# swimate_displayext.net
KiCad netlist of a schematic drawn in EAGLE
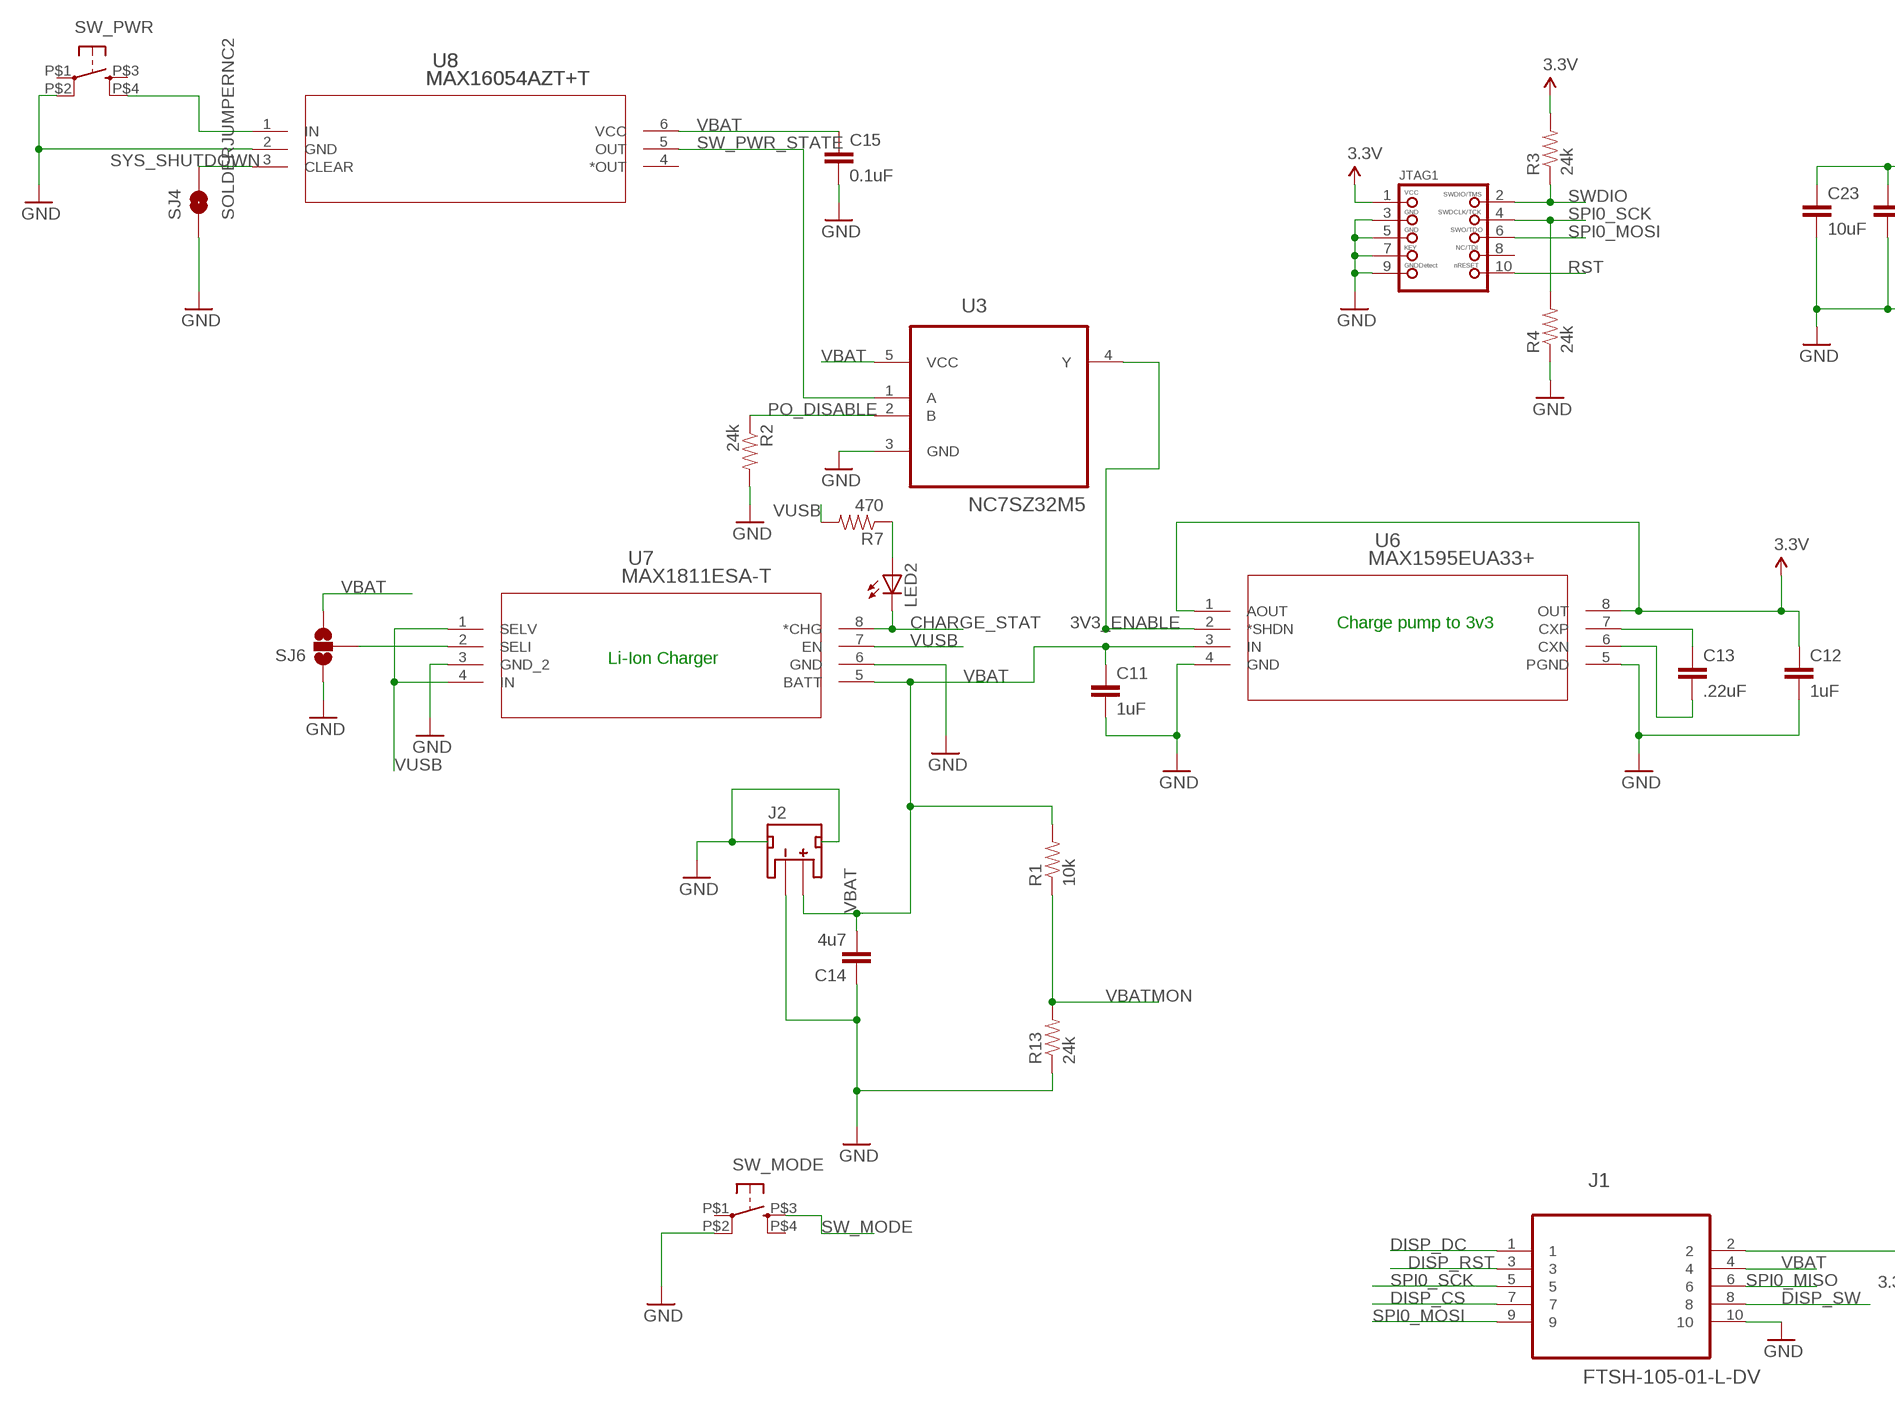
[diagram p0: schematic, sheet 1, part 1 of 2]
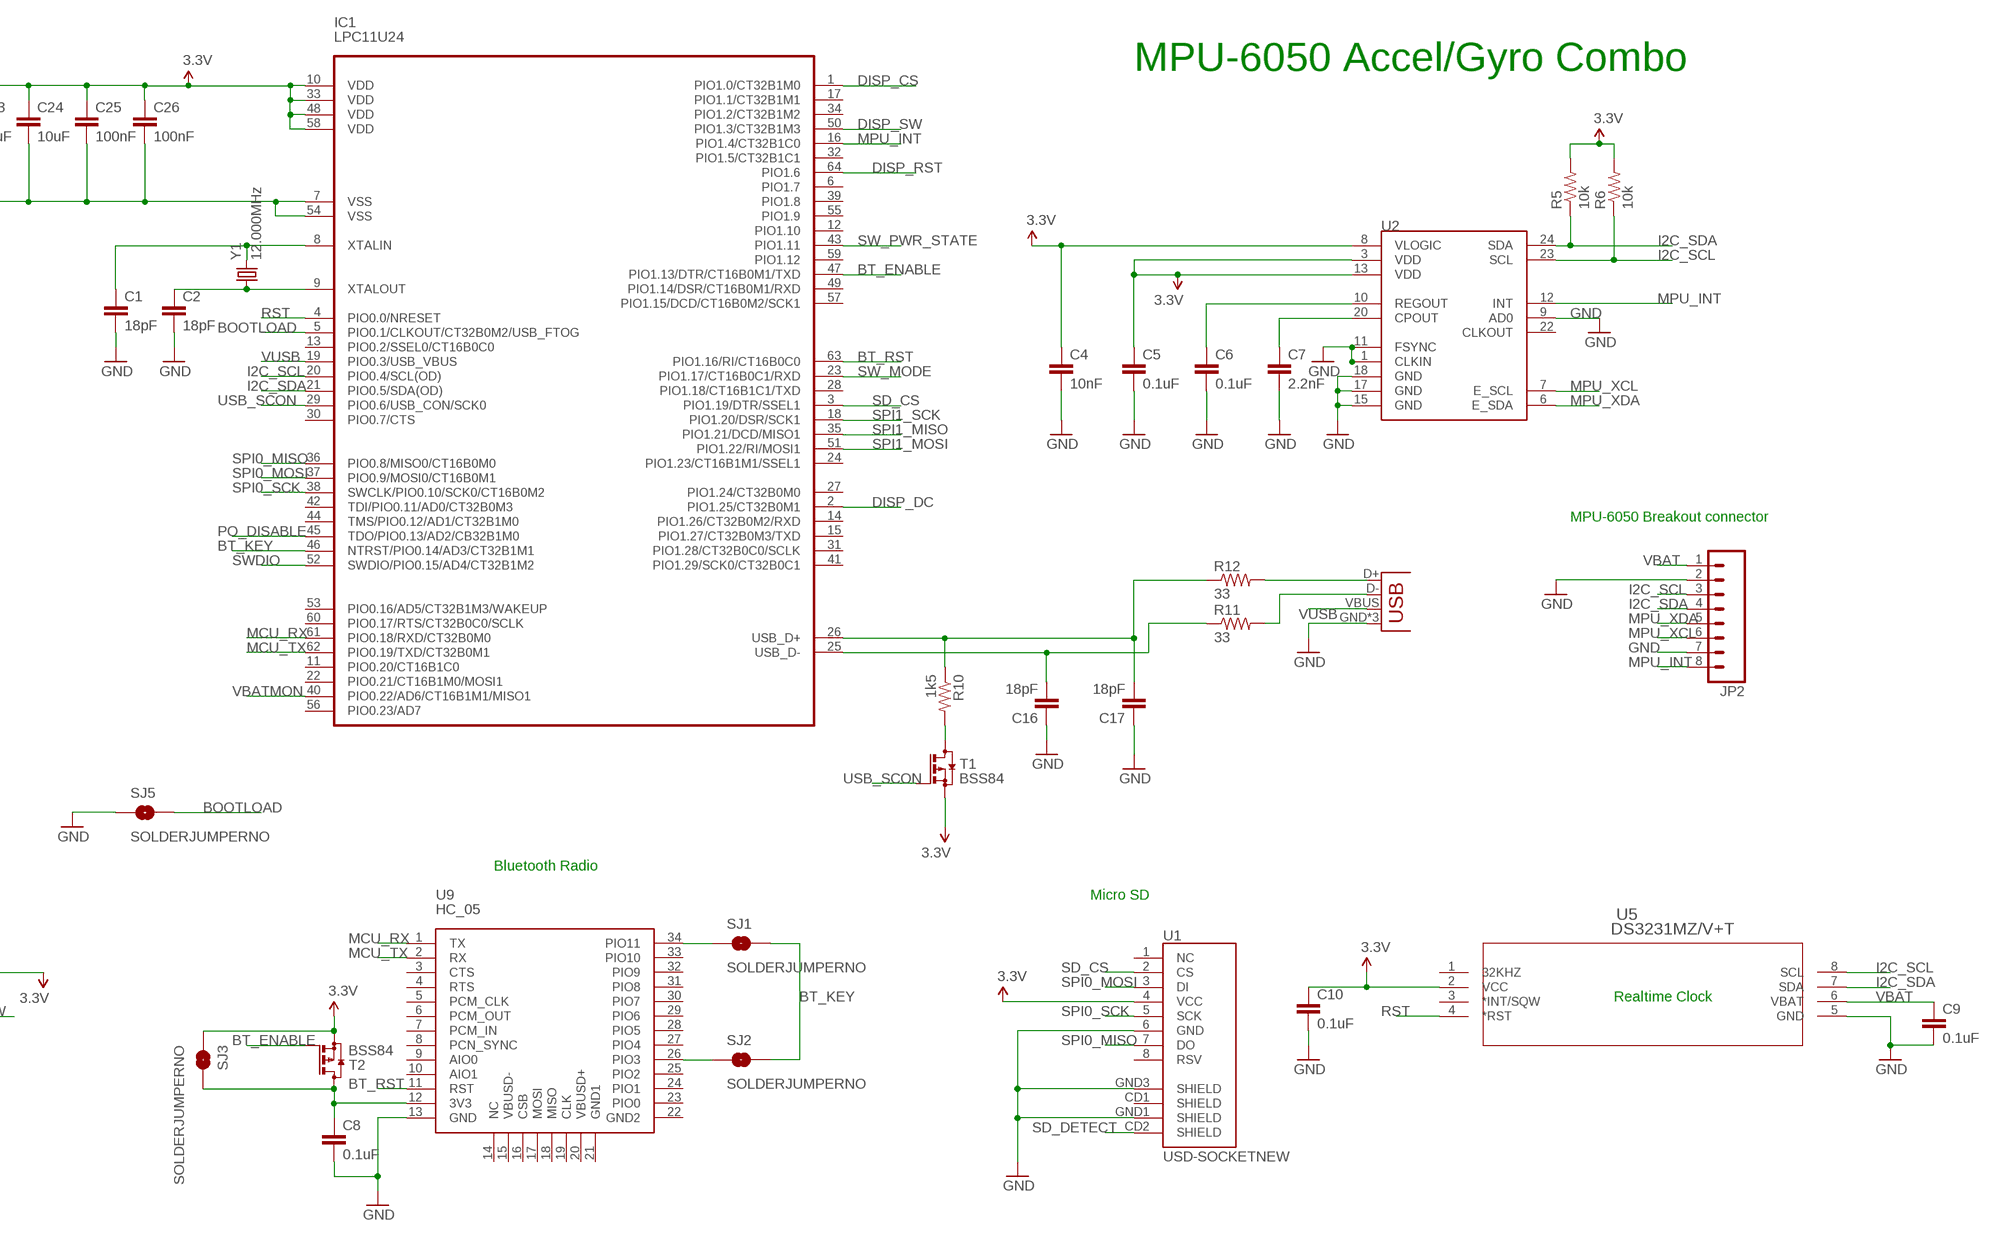
[diagram p1: schematic, sheet 1, part 2 of 2]

(export (version "E")
  (design (tool "Eeschema 10.0.6"))
  (components
    (comp (ref "C1")
      (value "18pF")
      (footprint "eagle-import:0805")
      (libsource (lib "eagle-import") (part "SparkFun-Passives_CAP0805"))
    )
    (comp (ref "C2")
      (value "18pF")
      (footprint "eagle-import:0805")
      (libsource (lib "eagle-import") (part "SparkFun-Passives_CAP0805"))
    )
    (comp (ref "C4")
      (value "10nF")
      (footprint "eagle-import:0805")
      (libsource (lib "eagle-import") (part "SparkFun-Passives_CAP0805"))
    )
    (comp (ref "C5")
      (value "0.1uF")
      (footprint "eagle-import:0805")
      (libsource (lib "eagle-import") (part "SparkFun-Passives_CAP0805"))
    )
    (comp (ref "C6")
      (value "0.1uF")
      (footprint "eagle-import:0805")
      (libsource (lib "eagle-import") (part "SparkFun-Passives_CAP0805"))
    )
    (comp (ref "C7")
      (value "2.2nF")
      (footprint "eagle-import:0805")
      (libsource (lib "eagle-import") (part "SparkFun-Passives_CAP0805"))
    )
    (comp (ref "C8")
      (value "0.1uF")
      (footprint "eagle-import:0805")
      (libsource (lib "eagle-import") (part "SparkFun-Passives_CAP0805"))
    )
    (comp (ref "C9")
      (value "0.1uF")
      (footprint "eagle-import:0805")
      (libsource (lib "eagle-import") (part "SparkFun-Passives_CAP0805"))
    )
    (comp (ref "C10")
      (value "0.1uF")
      (footprint "eagle-import:0805")
      (libsource (lib "eagle-import") (part "SparkFun-Passives_CAP0805"))
    )
    (comp (ref "C11")
      (value "1uF")
      (footprint "eagle-import:1206")
      (libsource (lib "eagle-import") (part "CAP1206"))
    )
    (comp (ref "C12")
      (value "1uF")
      (footprint "eagle-import:1206")
      (libsource (lib "eagle-import") (part "CAP1206"))
    )
    (comp (ref "C13")
      (value ".22uF")
      (footprint "eagle-import:0805")
      (libsource (lib "eagle-import") (part "SparkFun-Passives_CAP0805"))
    )
    (comp (ref "C14")
      (value "4u7")
      (footprint "eagle-import:1206")
      (libsource (lib "eagle-import") (part "SparkFun-Passives_CAP1206"))
    )
    (comp (ref "C15")
      (value "0.1uF")
      (footprint "eagle-import:0805")
      (libsource (lib "eagle-import") (part "SparkFun-Passives_CAP0805"))
    )
    (comp (ref "C16")
      (value "18pF")
      (footprint "eagle-import:0805")
      (libsource (lib "eagle-import") (part "SparkFun-Passives_CAP0805"))
    )
    (comp (ref "C17")
      (value "18pF")
      (footprint "eagle-import:0805")
      (libsource (lib "eagle-import") (part "SparkFun-Passives_CAP0805"))
    )
    (comp (ref "C23")
      (value "10uF")
      (footprint "eagle-import:0805")
      (libsource (lib "eagle-import") (part "CAP0805"))
    )
    (comp (ref "C24")
      (value "10uF")
      (footprint "eagle-import:0805")
      (libsource (lib "eagle-import") (part "CAP0805"))
    )
    (comp (ref "C25")
      (value "100nF")
      (footprint "eagle-import:0805")
      (libsource (lib "eagle-import") (part "CAP0805"))
    )
    (comp (ref "C26")
      (value "100nF")
      (footprint "eagle-import:0805")
      (libsource (lib "eagle-import") (part "CAP0805"))
    )
    (comp (ref "IC1")
      (value "LPC11U24")
      (footprint "eagle-import:MBED-ICS_LQFP64")
      (libsource (lib "eagle-import") (part "LPC11U24"))
    )
    (comp (ref "J1")
      (value "FTSH-105-01-L-DV")
      (footprint "eagle-import:SAMTEC_FTSH-105-01-L-DV")
      (libsource (lib "eagle-import") (part "FTSH-105-01-L-DV"))
    )
    (comp (ref "J2")
      (value "JST_2MM_MALE")
      (footprint "eagle-import:JST-2-SMD")
      (libsource (lib "eagle-import") (part "JST_2MM_MALE"))
    )
    (comp (ref "JP2")
      (value "M08")
      (footprint "eagle-import:1X08_PIN1_NO_SILK")
      (libsource (lib "eagle-import") (part "M08"))
    )
    (comp (ref "JP3")
      (value "USB-MICROB")
      (footprint "eagle-import:USB-MICROB")
      (libsource (lib "eagle-import") (part "USB-MICROB"))
    )
    (comp (ref "JTAG1")
      (value "JTAG-CORTEXM3")
      (footprint "eagle-import:2X05_1.27MM_SMT")
      (libsource (lib "eagle-import") (part "JTAG-CORTEXM3"))
    )
    (comp (ref "LED2")
      (value "LED0603")
      (footprint "eagle-import:LED-0603")
      (libsource (lib "eagle-import") (part "LED0603"))
    )
    (comp (ref "R1")
      (value "10k")
      (footprint "eagle-import:0603-RES")
      (libsource (lib "eagle-import") (part "RESISTOR0603-RES"))
    )
    (comp (ref "R2")
      (value "24k")
      (footprint "eagle-import:0805")
      (libsource (lib "eagle-import") (part "RESISTOR0805-RES"))
    )
    (comp (ref "R3")
      (value "24k")
      (footprint "eagle-import:0805")
      (libsource (lib "eagle-import") (part "RESISTOR0805-RES"))
    )
    (comp (ref "R4")
      (value "24k")
      (footprint "eagle-import:0805")
      (libsource (lib "eagle-import") (part "RESISTOR0805-RES"))
    )
    (comp (ref "R5")
      (value "10k")
      (footprint "eagle-import:0805")
      (libsource (lib "eagle-import") (part "RESISTOR0805-RES"))
    )
    (comp (ref "R6")
      (value "10k")
      (footprint "eagle-import:0805")
      (libsource (lib "eagle-import") (part "RESISTOR0805-RES"))
    )
    (comp (ref "R7")
      (value "470")
      (footprint "eagle-import:0805")
      (libsource (lib "eagle-import") (part "RESISTOR0805-RES"))
    )
    (comp (ref "R10")
      (value "1k5")
      (footprint "eagle-import:0805")
      (libsource (lib "eagle-import") (part "RESISTOR0805-RES"))
    )
    (comp (ref "R11")
      (value "33")
      (footprint "eagle-import:0805")
      (libsource (lib "eagle-import") (part "RESISTOR0805-RES"))
    )
    (comp (ref "R12")
      (value "33")
      (footprint "eagle-import:0805")
      (libsource (lib "eagle-import") (part "RESISTOR0805-RES"))
    )
    (comp (ref "R13")
      (value "24k")
      (footprint "eagle-import:0603-RES")
      (libsource (lib "eagle-import") (part "RESISTOR0603-RES"))
    )
    (comp (ref "SJ1")
      (value "SOLDERJUMPERNO")
      (footprint "eagle-import:SJ_2S-NO")
      (libsource (lib "eagle-import") (part "SOLDERJUMPERNO"))
    )
    (comp (ref "SJ2")
      (value "SOLDERJUMPERNO")
      (footprint "eagle-import:SJ_2S-NO")
      (libsource (lib "eagle-import") (part "SOLDERJUMPERNO"))
    )
    (comp (ref "SJ3")
      (value "SOLDERJUMPERNO")
      (footprint "eagle-import:SJ_2S-NO")
      (libsource (lib "eagle-import") (part "SOLDERJUMPERNO"))
    )
    (comp (ref "SJ4")
      (value "SOLDERJUMPERNC2")
      (footprint "eagle-import:SJ_2S-NOTRACE")
      (libsource (lib "eagle-import") (part "SOLDERJUMPERNC2"))
    )
    (comp (ref "SJ5")
      (value "SOLDERJUMPERNO")
      (footprint "eagle-import:SJ_2S-NO")
      (libsource (lib "eagle-import") (part "SOLDERJUMPERNO"))
    )
    (comp (ref "SJ6")
      (value "SOLDERJUMPER_2WAYS")
      (footprint "eagle-import:SJ_3")
      (libsource (lib "eagle-import") (part "SOLDERJUMPER_2WAYS"))
    )
    (comp (ref "SW_MODE")
      (value "TAC_SWITCHKSA_SEALED")
      (footprint "eagle-import:KSA_SEALED_TAC_SWITCH")
      (libsource (lib "eagle-import") (part "TAC_SWITCHKSA_SEALED"))
    )
    (comp (ref "SW_PWR")
      (value "TAC_SWITCHKSA_SEALED")
      (footprint "eagle-import:KSA_SEALED_TAC_SWITCH")
      (libsource (lib "eagle-import") (part "TAC_SWITCHKSA_SEALED"))
    )
    (comp (ref "T1")
      (value "BSS84")
      (footprint "eagle-import:SOT23")
      (libsource (lib "eagle-import") (part "BSS84"))
    )
    (comp (ref "T2")
      (value "BSS84")
      (footprint "eagle-import:SOT23")
      (libsource (lib "eagle-import") (part "BSS84"))
    )
    (comp (ref "U1")
      (value "USD-SOCKETNEW")
      (footprint "eagle-import:MICRO-SD-SOCKET-PP")
      (libsource (lib "eagle-import") (part "USD-SOCKETNEW"))
    )
    (comp (ref "U2")
      (value "MPU-9150QFN-24-NP")
      (footprint "eagle-import:QFN-24-NP")
      (libsource (lib "eagle-import") (part "MPU-9150QFN-24-NP"))
    )
    (comp (ref "U3")
      (value "NC7SZ32M5")
      (footprint "eagle-import:SOT95P280X145-5N")
      (libsource (lib "eagle-import") (part "NC7SZ32M5"))
    )
    (comp (ref "U5")
      (value "DS3231MZ/V+T")
      (footprint "eagle-import:21-0041B_8")
      (libsource (lib "eagle-import") (part "DS3231MZ/V+T"))
    )
    (comp (ref "U6")
      (value "MAX1595EUA33+")
      (footprint "eagle-import:21-0036K")
      (libsource (lib "eagle-import") (part "MAX1595EUA33+"))
    )
    (comp (ref "U7")
      (value "MAX1811ESA-T")
      (footprint "eagle-import:21-0041B_8")
      (libsource (lib "eagle-import") (part "MAX1811ESA-T"))
    )
    (comp (ref "U8")
      (value "MAX16054AZT+T")
      (footprint "eagle-import:21-0114C")
      (libsource (lib "eagle-import") (part "MAX16054AZT+T"))
    )
    (comp (ref "U9")
      (value "HC_05")
      (footprint "eagle-import:BLUETOOTH_SMD")
      (libsource (lib "eagle-import") (part "HC_05"))
    )
    (comp (ref "Y1")
      (value "12.000MHz")
      (footprint "eagle-import:CRYSTAL-SMD-10.5X4.8-2PIN")
      (libsource (lib "eagle-import") (part "CRYSTAL10.5X4.8"))
    )
  )
  (nets
    (net (code "1") (name "/3V3_ENABLE") (class "Default")
      (node (ref "U3") (pin "4") (pinfunction "Y_4") (pintype "output"))
      (node (ref "U6") (pin "2") (pinfunction "*SHDN_2") (pintype "passive"))
    )
    (net (code "2") (name "/BOOTLOAD") (class "Default")
      (node (ref "IC1") (pin "5") (pinfunction "PIO0.1/CLKOUT/CT32B0M2/USB_FTOG_5") (pintype "bidirectional"))
      (node (ref "SJ5") (pin "2") (pinfunction "2_2") (pintype "passive"))
    )
    (net (code "3") (name "/BT_ENABLE") (class "Default")
      (node (ref "IC1") (pin "47") (pinfunction "PIO1.13/DTR/CT16B0M1/TXD_47") (pintype "bidirectional"))
      (node (ref "T2") (pin "1") (pinfunction "G_1") (pintype "passive"))
    )
    (net (code "4") (name "/BT_KEY") (class "Default")
      (node (ref "IC1") (pin "46") (pinfunction "NTRST/PIO0.14/AD3/CT32B1M1_46") (pintype "bidirectional"))
      (node (ref "SJ1") (pin "2") (pinfunction "2_2") (pintype "passive"))
      (node (ref "SJ2") (pin "2") (pinfunction "2_2") (pintype "passive"))
    )
    (net (code "5") (name "/BT_RST") (class "Default")
      (node (ref "IC1") (pin "63") (pinfunction "PIO1.16/RI/CT16B0C0_63") (pintype "bidirectional"))
      (node (ref "U9") (pin "11") (pinfunction "RST_11") (pintype "bidirectional"))
    )
    (net (code "6") (name "/CHARGE_STAT") (class "Default")
      (node (ref "LED2") (pin "C") (pinfunction "C_C") (pintype "passive"))
      (node (ref "U7") (pin "8") (pinfunction "*CHG_8") (pintype "bidirectional"))
    )
    (net (code "7") (name "/DISP_CS") (class "Default")
      (node (ref "IC1") (pin "1") (pinfunction "PIO1.0/CT32B1M0_1") (pintype "bidirectional"))
      (node (ref "J1") (pin "7") (pinfunction "7_7") (pintype "passive"))
    )
    (net (code "8") (name "/DISP_DC") (class "Default")
      (node (ref "IC1") (pin "2") (pinfunction "PIO1.25/CT32B0M1_2") (pintype "bidirectional"))
      (node (ref "J1") (pin "1") (pinfunction "1_1") (pintype "passive"))
    )
    (net (code "9") (name "/DISP_RST") (class "Default")
      (node (ref "IC1") (pin "64") (pinfunction "PIO1.6_64") (pintype "bidirectional"))
      (node (ref "J1") (pin "3") (pinfunction "3_3") (pintype "passive"))
    )
    (net (code "10") (name "/DISP_SW") (class "Default")
      (node (ref "IC1") (pin "50") (pinfunction "PIO1.3/CT32B1M3_50") (pintype "bidirectional"))
      (node (ref "J1") (pin "8") (pinfunction "8_8") (pintype "passive"))
    )
    (net (code "11") (name "/I2C_SCL") (class "Default")
      (node (ref "IC1") (pin "20") (pinfunction "PIO0.4/SCL(OD)_20") (pintype "bidirectional"))
      (node (ref "JP2") (pin "3") (pinfunction "3_3") (pintype "passive"))
      (node (ref "R6") (pin "1") (pinfunction "1_1") (pintype "passive"))
      (node (ref "U2") (pin "23") (pinfunction "SCL_23") (pintype "bidirectional"))
      (node (ref "U5") (pin "8") (pinfunction "SCL_8") (pintype "passive"))
    )
    (net (code "12") (name "/I2C_SDA") (class "Default")
      (node (ref "IC1") (pin "21") (pinfunction "PIO0.5/SDA(OD)_21") (pintype "bidirectional"))
      (node (ref "JP2") (pin "4") (pinfunction "4_4") (pintype "passive"))
      (node (ref "R5") (pin "1") (pinfunction "1_1") (pintype "passive"))
      (node (ref "U2") (pin "24") (pinfunction "SDA_24") (pintype "bidirectional"))
      (node (ref "U5") (pin "7") (pinfunction "SDA_7") (pintype "passive"))
    )
    (net (code "13") (name "/MCU_RX") (class "Default")
      (node (ref "IC1") (pin "61") (pinfunction "PIO0.18/RXD/CT32B0M0_61") (pintype "bidirectional"))
      (node (ref "U9") (pin "1") (pinfunction "TX_1") (pintype "bidirectional"))
    )
    (net (code "14") (name "/MCU_TX") (class "Default")
      (node (ref "IC1") (pin "62") (pinfunction "PIO0.19/TXD/CT32B0M1_62") (pintype "bidirectional"))
      (node (ref "U9") (pin "2") (pinfunction "RX_2") (pintype "bidirectional"))
    )
    (net (code "15") (name "/MPU_INT") (class "Default")
      (node (ref "IC1") (pin "16") (pinfunction "PIO1.4/CT32B1C0_16") (pintype "bidirectional"))
      (node (ref "JP2") (pin "8") (pinfunction "8_8") (pintype "passive"))
      (node (ref "U2") (pin "12") (pinfunction "INT_12") (pintype "bidirectional"))
    )
    (net (code "16") (name "/MPU_XCL") (class "Default")
      (node (ref "JP2") (pin "6") (pinfunction "6_6") (pintype "passive"))
      (node (ref "U2") (pin "7") (pinfunction "E_SCL_7") (pintype "bidirectional"))
    )
    (net (code "17") (name "/MPU_XDA") (class "Default")
      (node (ref "JP2") (pin "5") (pinfunction "5_5") (pintype "passive"))
      (node (ref "U2") (pin "6") (pinfunction "E_SDA_6") (pintype "bidirectional"))
    )
    (net (code "18") (name "/PO_DISABLE") (class "Default")
      (node (ref "IC1") (pin "45") (pinfunction "TDO/PIO0.13/AD2/CB32B1M0_45") (pintype "bidirectional"))
      (node (ref "R2") (pin "1") (pinfunction "1_1") (pintype "passive"))
      (node (ref "U3") (pin "2") (pinfunction "B_2") (pintype "input"))
    )
    (net (code "19") (name "/RST") (class "Default")
      (node (ref "IC1") (pin "4") (pinfunction "PIO0.0/NRESET_4") (pintype "bidirectional"))
      (node (ref "JTAG1") (pin "10") (pinfunction "10_10") (pintype "passive"))
      (node (ref "U5") (pin "4") (pinfunction "*RST_4") (pintype "passive"))
    )
    (net (code "20") (name "/SD_CS") (class "Default")
      (node (ref "IC1") (pin "3") (pinfunction "PIO1.19/DTR/SSEL1_3") (pintype "bidirectional"))
      (node (ref "U1") (pin "2") (pinfunction "CS_2") (pintype "bidirectional"))
    )
    (net (code "21") (name "/SD_DETECT") (class "Default")
      (node (ref "U1") (pin "CD2") (pinfunction "SHIELD_CD2") (pintype "bidirectional"))
    )
    (net (code "22") (name "/SPI0_MISO") (class "Default")
      (node (ref "IC1") (pin "36") (pinfunction "PIO0.8/MISO0/CT16B0M0_36") (pintype "bidirectional"))
      (node (ref "J1") (pin "6") (pinfunction "6_6") (pintype "passive"))
      (node (ref "U1") (pin "7") (pinfunction "DO_7") (pintype "bidirectional"))
    )
    (net (code "23") (name "/SPI0_MOSI") (class "Default")
      (node (ref "IC1") (pin "37") (pinfunction "PIO0.9/MOSI0/CT16B0M1_37") (pintype "bidirectional"))
      (node (ref "J1") (pin "9") (pinfunction "9_9") (pintype "passive"))
      (node (ref "JTAG1") (pin "6") (pinfunction "6_6") (pintype "passive"))
      (node (ref "U1") (pin "3") (pinfunction "DI_3") (pintype "bidirectional"))
    )
    (net (code "24") (name "/SPI0_SCK") (class "Default")
      (node (ref "IC1") (pin "38") (pinfunction "SWCLK/PIO0.10/SCK0/CT16B0M2_38") (pintype "bidirectional"))
      (node (ref "J1") (pin "5") (pinfunction "5_5") (pintype "passive"))
      (node (ref "JTAG1") (pin "4") (pinfunction "4_4") (pintype "passive"))
      (node (ref "R4") (pin "2") (pinfunction "2_2") (pintype "passive"))
      (node (ref "U1") (pin "5") (pinfunction "SCK_5") (pintype "bidirectional"))
    )
    (net (code "25") (name "/SPI1_MISO") (class "Default")
      (node (ref "IC1") (pin "35") (pinfunction "PIO1.21/DCD/MISO1_35") (pintype "bidirectional"))
    )
    (net (code "26") (name "/SPI1_MOSI") (class "Default")
      (node (ref "IC1") (pin "51") (pinfunction "PIO1.22/RI/MOSI1_51") (pintype "bidirectional"))
    )
    (net (code "27") (name "/SPI1_SCK") (class "Default")
      (node (ref "IC1") (pin "18") (pinfunction "PIO1.20/DSR/SCK1_18") (pintype "bidirectional"))
    )
    (net (code "28") (name "/SWDIO") (class "Default")
      (node (ref "IC1") (pin "52") (pinfunction "SWDIO/PIO0.15/AD4/CT32B1M2_52") (pintype "bidirectional"))
      (node (ref "JTAG1") (pin "2") (pinfunction "2_2") (pintype "passive"))
      (node (ref "R3") (pin "1") (pinfunction "1_1") (pintype "passive"))
    )
    (net (code "29") (name "/SW_MODE") (class "Default")
      (node (ref "IC1") (pin "23") (pinfunction "PIO1.17/CT16B0C1/RXD_23") (pintype "bidirectional"))
      (node (ref "SW_MODE") (pin "P$3") (pinfunction "3_P$3") (pintype "passive"))
    )
    (net (code "30") (name "/SW_PWR_STATE") (class "Default")
      (node (ref "IC1") (pin "43") (pinfunction "PIO1.11_43") (pintype "bidirectional"))
      (node (ref "U3") (pin "1") (pinfunction "A_1") (pintype "input"))
      (node (ref "U8") (pin "5") (pinfunction "OUT_5") (pintype "output"))
    )
    (net (code "31") (name "/SYS_SHUTDOWN") (class "Default")
      (node (ref "SJ4") (pin "2") (pinfunction "2_2") (pintype "passive"))
      (node (ref "U8") (pin "3") (pinfunction "CLEAR_3") (pintype "bidirectional"))
    )
    (net (code "32") (name "/USB_SCON") (class "Default")
      (node (ref "IC1") (pin "29") (pinfunction "PIO0.6/USB_CON/SCK0_29") (pintype "bidirectional"))
      (node (ref "T1") (pin "1") (pinfunction "G_1") (pintype "passive"))
    )
    (net (code "33") (name "/VBAT") (class "Default")
      (node (ref "C11") (pin "1") (pinfunction "1_1") (pintype "passive"))
      (node (ref "C14") (pin "2") (pinfunction "2_2") (pintype "passive"))
      (node (ref "C15") (pin "1") (pinfunction "1_1") (pintype "passive"))
      (node (ref "C9") (pin "1") (pinfunction "1_1") (pintype "passive"))
      (node (ref "J1") (pin "4") (pinfunction "4_4") (pintype "passive"))
      (node (ref "J2") (pin "2") (pinfunction "+_2") (pintype "bidirectional"))
      (node (ref "JP2") (pin "1") (pinfunction "1_1") (pintype "passive"))
      (node (ref "R1") (pin "2") (pinfunction "2_2") (pintype "passive"))
      (node (ref "SJ6") (pin "3") (pinfunction "3_3") (pintype "passive"))
      (node (ref "U3") (pin "5") (pinfunction "VCC_5") (pintype "power_in"))
      (node (ref "U5") (pin "6") (pinfunction "VBAT_6") (pintype "power_in"))
      (node (ref "U6") (pin "3") (pinfunction "IN_3") (pintype "input"))
      (node (ref "U7") (pin "5") (pinfunction "BATT_5") (pintype "bidirectional"))
      (node (ref "U8") (pin "6") (pinfunction "VCC_6") (pintype "power_in"))
    )
    (net (code "34") (name "/VBATMON") (class "Default")
      (node (ref "IC1") (pin "40") (pinfunction "PIO0.22/AD6/CT16B1M1/MISO1_40") (pintype "bidirectional"))
      (node (ref "R1") (pin "1") (pinfunction "1_1") (pintype "passive"))
      (node (ref "R13") (pin "2") (pinfunction "2_2") (pintype "passive"))
    )
    (net (code "35") (name "/VUSB") (class "Default")
      (node (ref "IC1") (pin "19") (pinfunction "PIO0.3/USB_VBUS_19") (pintype "bidirectional"))
      (node (ref "JP3") (pin "VBUS") (pinfunction "VBUS_VBUS") (pintype "bidirectional"))
      (node (ref "R7") (pin "2") (pinfunction "2_2") (pintype "passive"))
      (node (ref "U7") (pin "1") (pinfunction "SELV_1") (pintype "bidirectional"))
      (node (ref "U7") (pin "4") (pinfunction "IN_4") (pintype "input"))
      (node (ref "U7") (pin "7") (pinfunction "EN_7") (pintype "bidirectional"))
    )
    (net (code "36") (name "3.3V") (class "Default")
      (node (ref "C10") (pin "1") (pinfunction "1_1") (pintype "passive"))
      (node (ref "C12") (pin "1") (pinfunction "1_1") (pintype "passive"))
      (node (ref "C23") (pin "1") (pinfunction "1_1") (pintype "passive"))
      (node (ref "C24") (pin "1") (pinfunction "1_1") (pintype "passive"))
      (node (ref "C25") (pin "1") (pinfunction "1_1") (pintype "passive"))
      (node (ref "C26") (pin "1") (pinfunction "1_1") (pintype "passive"))
      (node (ref "C4") (pin "1") (pinfunction "1_1") (pintype "passive"))
      (node (ref "C5") (pin "1") (pinfunction "1_1") (pintype "passive"))
      (node (ref "IC1") (pin "10") (pinfunction "VDD_10") (pintype "bidirectional"))
      (node (ref "IC1") (pin "33") (pinfunction "VDD_33") (pintype "bidirectional"))
      (node (ref "IC1") (pin "48") (pinfunction "VDD_48") (pintype "bidirectional"))
      (node (ref "IC1") (pin "58") (pinfunction "VDD_58") (pintype "bidirectional"))
      (node (ref "J1") (pin "2") (pinfunction "2_2") (pintype "passive"))
      (node (ref "JTAG1") (pin "1") (pinfunction "1_1") (pintype "passive"))
      (node (ref "R3") (pin "2") (pinfunction "2_2") (pintype "passive"))
      (node (ref "R5") (pin "2") (pinfunction "2_2") (pintype "passive"))
      (node (ref "R6") (pin "2") (pinfunction "2_2") (pintype "passive"))
      (node (ref "SJ3") (pin "1") (pinfunction "1_1") (pintype "passive"))
      (node (ref "T1") (pin "2") (pinfunction "S_2") (pintype "passive"))
      (node (ref "T2") (pin "2") (pinfunction "S_2") (pintype "passive"))
      (node (ref "U1") (pin "4") (pinfunction "VCC_4") (pintype "bidirectional"))
      (node (ref "U2") (pin "13") (pinfunction "VDD_13") (pintype "bidirectional"))
      (node (ref "U2") (pin "3") (pinfunction "VDD_3") (pintype "bidirectional"))
      (node (ref "U2") (pin "8") (pinfunction "VLOGIC_8") (pintype "bidirectional"))
      (node (ref "U5") (pin "2") (pinfunction "VCC_2") (pintype "power_in"))
      (node (ref "U6") (pin "1") (pinfunction "AOUT_1") (pintype "output"))
      (node (ref "U6") (pin "8") (pinfunction "OUT_8") (pintype "output"))
    )
    (net (code "37") (name "GND") (class "Default")
      (node (ref "C1") (pin "2") (pinfunction "2_2") (pintype "passive"))
      (node (ref "C10") (pin "2") (pinfunction "2_2") (pintype "passive"))
      (node (ref "C11") (pin "2") (pinfunction "2_2") (pintype "passive"))
      (node (ref "C12") (pin "2") (pinfunction "2_2") (pintype "passive"))
      (node (ref "C14") (pin "1") (pinfunction "1_1") (pintype "passive"))
      (node (ref "C15") (pin "2") (pinfunction "2_2") (pintype "passive"))
      (node (ref "C16") (pin "1") (pinfunction "1_1") (pintype "passive"))
      (node (ref "C17") (pin "1") (pinfunction "1_1") (pintype "passive"))
      (node (ref "C2") (pin "2") (pinfunction "2_2") (pintype "passive"))
      (node (ref "C23") (pin "2") (pinfunction "2_2") (pintype "passive"))
      (node (ref "C24") (pin "2") (pinfunction "2_2") (pintype "passive"))
      (node (ref "C25") (pin "2") (pinfunction "2_2") (pintype "passive"))
      (node (ref "C26") (pin "2") (pinfunction "2_2") (pintype "passive"))
      (node (ref "C4") (pin "2") (pinfunction "2_2") (pintype "passive"))
      (node (ref "C5") (pin "2") (pinfunction "2_2") (pintype "passive"))
      (node (ref "C6") (pin "2") (pinfunction "2_2") (pintype "passive"))
      (node (ref "C7") (pin "2") (pinfunction "2_2") (pintype "passive"))
      (node (ref "C8") (pin "2") (pinfunction "2_2") (pintype "passive"))
      (node (ref "C9") (pin "2") (pinfunction "2_2") (pintype "passive"))
      (node (ref "IC1") (pin "54") (pinfunction "VSS_54") (pintype "bidirectional"))
      (node (ref "IC1") (pin "7") (pinfunction "VSS_7") (pintype "bidirectional"))
      (node (ref "J1") (pin "10") (pinfunction "10_10") (pintype "passive"))
      (node (ref "J2") (pin "1") (pinfunction "-_1") (pintype "bidirectional"))
      (node (ref "J2") (pin "NC1") (pinfunction "PAD1_NC1") (pintype "bidirectional"))
      (node (ref "J2") (pin "NC2") (pinfunction "PAD2_NC2") (pintype "bidirectional"))
      (node (ref "JP2") (pin "2") (pinfunction "2_2") (pintype "passive"))
      (node (ref "JP2") (pin "7") (pinfunction "7_7") (pintype "passive"))
      (node (ref "JP3") (pin "GND") (pinfunction "GND_GND") (pintype "bidirectional"))
      (node (ref "JP3") (pin "MT1") (pinfunction "GND_MT1") (pintype "bidirectional"))
      (node (ref "JP3") (pin "MT2") (pinfunction "GND_MT2") (pintype "bidirectional"))
      (node (ref "JTAG1") (pin "3") (pinfunction "3_3") (pintype "passive"))
      (node (ref "JTAG1") (pin "5") (pinfunction "5_5") (pintype "passive"))
      (node (ref "JTAG1") (pin "7") (pinfunction "7_7") (pintype "passive"))
      (node (ref "JTAG1") (pin "9") (pinfunction "9_9") (pintype "passive"))
      (node (ref "R13") (pin "1") (pinfunction "1_1") (pintype "passive"))
      (node (ref "R2") (pin "2") (pinfunction "2_2") (pintype "passive"))
      (node (ref "R4") (pin "1") (pinfunction "1_1") (pintype "passive"))
      (node (ref "SJ4") (pin "1") (pinfunction "1_1") (pintype "passive"))
      (node (ref "SJ5") (pin "1") (pinfunction "1_1") (pintype "passive"))
      (node (ref "SJ6") (pin "1") (pinfunction "1_1") (pintype "passive"))
      (node (ref "SW_MODE") (pin "P$2") (pinfunction "2_P$2") (pintype "passive"))
      (node (ref "SW_PWR") (pin "P$2") (pinfunction "2_P$2") (pintype "passive"))
      (node (ref "U1") (pin "6") (pinfunction "GND_6") (pintype "bidirectional"))
      (node (ref "U1") (pin "GND1") (pinfunction "SHIELD_GND1") (pintype "bidirectional"))
      (node (ref "U1") (pin "GND3") (pinfunction "SHIELD_GND3") (pintype "bidirectional"))
      (node (ref "U2") (pin "1") (pinfunction "CLKIN_1") (pintype "bidirectional"))
      (node (ref "U2") (pin "11") (pinfunction "FSYNC_11") (pintype "bidirectional"))
      (node (ref "U2") (pin "15") (pinfunction "GND_15") (pintype "bidirectional"))
      (node (ref "U2") (pin "17") (pinfunction "GND_17") (pintype "bidirectional"))
      (node (ref "U2") (pin "18") (pinfunction "GND_18") (pintype "bidirectional"))
      (node (ref "U2") (pin "9") (pinfunction "AD0_9") (pintype "bidirectional"))
      (node (ref "U3") (pin "3") (pinfunction "GND_3") (pintype "passive"))
      (node (ref "U5") (pin "5") (pinfunction "GND_5") (pintype "power_in"))
      (node (ref "U6") (pin "4") (pinfunction "GND_4") (pintype "power_in"))
      (node (ref "U6") (pin "5") (pinfunction "PGND_5") (pintype "power_in"))
      (node (ref "U7") (pin "3") (pinfunction "GND_2_3") (pintype "power_in"))
      (node (ref "U7") (pin "6") (pinfunction "GND_6") (pintype "power_in"))
      (node (ref "U8") (pin "2") (pinfunction "GND_2") (pintype "power_in"))
      (node (ref "U9") (pin "13") (pinfunction "GND_13") (pintype "bidirectional"))
    )
    (net (code "38") (name "Net-(IC1-USB_D+)") (class "Default")
      (node (ref "C17") (pin "2") (pinfunction "2_2") (pintype "passive"))
      (node (ref "IC1") (pin "26") (pinfunction "USB_D+_26") (pintype "bidirectional"))
      (node (ref "R10") (pin "1") (pinfunction "1_1") (pintype "passive"))
      (node (ref "R12") (pin "1") (pinfunction "1_1") (pintype "passive"))
    )
    (net (code "39") (name "Net-(IC1-USB_D-)") (class "Default")
      (node (ref "C16") (pin "2") (pinfunction "2_2") (pintype "passive"))
      (node (ref "IC1") (pin "25") (pinfunction "USB_D-_25") (pintype "bidirectional"))
      (node (ref "R11") (pin "1") (pinfunction "1_1") (pintype "passive"))
    )
    (net (code "40") (name "Net-(IC1-XTALIN)") (class "Default")
      (node (ref "C1") (pin "1") (pinfunction "1_1") (pintype "passive"))
      (node (ref "IC1") (pin "8") (pinfunction "XTALIN_8") (pintype "bidirectional"))
      (node (ref "Y1") (pin "P$2") (pinfunction "2_P$2") (pintype "passive"))
    )
    (net (code "41") (name "Net-(IC1-XTALOUT)") (class "Default")
      (node (ref "C2") (pin "1") (pinfunction "1_1") (pintype "passive"))
      (node (ref "IC1") (pin "9") (pinfunction "XTALOUT_9") (pintype "bidirectional"))
      (node (ref "Y1") (pin "P$1") (pinfunction "1_P$1") (pintype "passive"))
    )
    (net (code "42") (name "Net-(JP3-PadD+)") (class "Default")
      (node (ref "JP3") (pin "D+") (pinfunction "D+_D+") (pintype "bidirectional"))
      (node (ref "R12") (pin "2") (pinfunction "2_2") (pintype "passive"))
    )
    (net (code "43") (name "Net-(JP3-PadD-)") (class "Default")
      (node (ref "JP3") (pin "D-") (pinfunction "D-_D-") (pintype "bidirectional"))
      (node (ref "R11") (pin "2") (pinfunction "2_2") (pintype "passive"))
    )
    (net (code "44") (name "Net-(LED2-PadA)") (class "Default")
      (node (ref "LED2") (pin "A") (pinfunction "A_A") (pintype "passive"))
      (node (ref "R7") (pin "1") (pinfunction "1_1") (pintype "passive"))
    )
    (net (code "45") (name "Net-(SW_PWR-4)") (class "Default")
      (node (ref "SW_PWR") (pin "P$4") (pinfunction "4_P$4") (pintype "passive"))
      (node (ref "U8") (pin "1") (pinfunction "IN_1") (pintype "input"))
    )
    (net (code "46") (name "Net-(T1-D)") (class "Default")
      (node (ref "R10") (pin "2") (pinfunction "2_2") (pintype "passive"))
      (node (ref "T1") (pin "3") (pinfunction "D_3") (pintype "passive"))
    )
    (net (code "47") (name "Net-(T2-D)") (class "Default")
      (node (ref "C8") (pin "1") (pinfunction "1_1") (pintype "passive"))
      (node (ref "SJ3") (pin "2") (pinfunction "2_2") (pintype "passive"))
      (node (ref "T2") (pin "3") (pinfunction "D_3") (pintype "passive"))
      (node (ref "U9") (pin "12") (pinfunction "3V3_12") (pintype "bidirectional"))
    )
    (net (code "48") (name "Net-(U2-CPOUT)") (class "Default")
      (node (ref "C7") (pin "1") (pinfunction "1_1") (pintype "passive"))
      (node (ref "U2") (pin "20") (pinfunction "CPOUT_20") (pintype "bidirectional"))
    )
    (net (code "49") (name "Net-(U2-REGOUT)") (class "Default")
      (node (ref "C6") (pin "1") (pinfunction "1_1") (pintype "passive"))
      (node (ref "U2") (pin "10") (pinfunction "REGOUT_10") (pintype "bidirectional"))
    )
    (net (code "50") (name "Net-(U6-CXN)") (class "Default")
      (node (ref "C13") (pin "2") (pinfunction "2_2") (pintype "passive"))
      (node (ref "U6") (pin "6") (pinfunction "CXN_6") (pintype "passive"))
    )
    (net (code "51") (name "Net-(U6-CXP)") (class "Default")
      (node (ref "C13") (pin "1") (pinfunction "1_1") (pintype "passive"))
      (node (ref "U6") (pin "7") (pinfunction "CXP_7") (pintype "passive"))
    )
    (net (code "52") (name "Net-(U7-SELI)") (class "Default")
      (node (ref "SJ6") (pin "2") (pinfunction "2_2") (pintype "passive"))
      (node (ref "U7") (pin "2") (pinfunction "SELI_2") (pintype "bidirectional"))
    )
    (net (code "53") (name "Net-(U9-PIO3)") (class "Default")
      (node (ref "SJ2") (pin "1") (pinfunction "1_1") (pintype "passive"))
      (node (ref "U9") (pin "26") (pinfunction "PIO3_26") (pintype "bidirectional"))
    )
    (net (code "54") (name "Net-(U9-PIO11)") (class "Default")
      (node (ref "SJ1") (pin "1") (pinfunction "1_1") (pintype "passive"))
      (node (ref "U9") (pin "34") (pinfunction "PIO11_34") (pintype "bidirectional"))
    )
    (net (code "55") (name "unconnected-(IC1-PIO0.2{slash}SSEL0{slash}CT16B0C0-Pad13)") (class "Default")
      (node (ref "IC1") (pin "13") (pinfunction "PIO0.2/SSEL0/CT16B0C0_13") (pintype "bidirectional"))
    )
    (net (code "56") (name "unconnected-(IC1-PIO0.7{slash}CTS-Pad30)") (class "Default")
      (node (ref "IC1") (pin "30") (pinfunction "PIO0.7/CTS_30") (pintype "bidirectional"))
    )
    (net (code "57") (name "unconnected-(IC1-PIO0.16{slash}AD5{slash}CT32B1M3{slash}WAKEUP-Pad53)") (class "Default")
      (node (ref "IC1") (pin "53") (pinfunction "PIO0.16/AD5/CT32B1M3/WAKEUP_53") (pintype "bidirectional"))
    )
    (net (code "58") (name "unconnected-(IC1-PIO0.17{slash}RTS{slash}CT32B0C0{slash}SCLK-Pad60)") (class "Default")
      (node (ref "IC1") (pin "60") (pinfunction "PIO0.17/RTS/CT32B0C0/SCLK_60") (pintype "bidirectional"))
    )
    (net (code "59") (name "unconnected-(IC1-PIO0.20{slash}CT16B1C0-Pad11)") (class "Default")
      (node (ref "IC1") (pin "11") (pinfunction "PIO0.20/CT16B1C0_11") (pintype "bidirectional"))
    )
    (net (code "60") (name "unconnected-(IC1-PIO0.21{slash}CT16B1M0{slash}MOSI1-Pad22)") (class "Default")
      (node (ref "IC1") (pin "22") (pinfunction "PIO0.21/CT16B1M0/MOSI1_22") (pintype "bidirectional"))
    )
    (net (code "61") (name "unconnected-(IC1-PIO0.23{slash}AD7-Pad56)") (class "Default")
      (node (ref "IC1") (pin "56") (pinfunction "PIO0.23/AD7_56") (pintype "bidirectional"))
    )
    (net (code "62") (name "unconnected-(IC1-PIO1.1{slash}CT32B1M1-Pad17)") (class "Default")
      (node (ref "IC1") (pin "17") (pinfunction "PIO1.1/CT32B1M1_17") (pintype "bidirectional"))
    )
    (net (code "63") (name "unconnected-(IC1-PIO1.2{slash}CT32B1M2-Pad34)") (class "Default")
      (node (ref "IC1") (pin "34") (pinfunction "PIO1.2/CT32B1M2_34") (pintype "bidirectional"))
    )
    (net (code "64") (name "unconnected-(IC1-PIO1.5{slash}CT32B1C1-Pad32)") (class "Default")
      (node (ref "IC1") (pin "32") (pinfunction "PIO1.5/CT32B1C1_32") (pintype "bidirectional"))
    )
    (net (code "65") (name "unconnected-(IC1-PIO1.7-Pad6)") (class "Default")
      (node (ref "IC1") (pin "6") (pinfunction "PIO1.7_6") (pintype "bidirectional"))
    )
    (net (code "66") (name "unconnected-(IC1-PIO1.8-Pad39)") (class "Default")
      (node (ref "IC1") (pin "39") (pinfunction "PIO1.8_39") (pintype "bidirectional"))
    )
    (net (code "67") (name "unconnected-(IC1-PIO1.9-Pad55)") (class "Default")
      (node (ref "IC1") (pin "55") (pinfunction "PIO1.9_55") (pintype "bidirectional"))
    )
    (net (code "68") (name "unconnected-(IC1-PIO1.10-Pad12)") (class "Default")
      (node (ref "IC1") (pin "12") (pinfunction "PIO1.10_12") (pintype "bidirectional"))
    )
    (net (code "69") (name "unconnected-(IC1-PIO1.12-Pad59)") (class "Default")
      (node (ref "IC1") (pin "59") (pinfunction "PIO1.12_59") (pintype "bidirectional"))
    )
    (net (code "70") (name "unconnected-(IC1-PIO1.14{slash}DSR{slash}CT16B0M1{slash}RXD-Pad49)") (class "Default")
      (node (ref "IC1") (pin "49") (pinfunction "PIO1.14/DSR/CT16B0M1/RXD_49") (pintype "bidirectional"))
    )
    (net (code "71") (name "unconnected-(IC1-PIO1.15{slash}DCD{slash}CT16B0M2{slash}SCK1-Pad57)") (class "Default")
      (node (ref "IC1") (pin "57") (pinfunction "PIO1.15/DCD/CT16B0M2/SCK1_57") (pintype "bidirectional"))
    )
    (net (code "72") (name "unconnected-(IC1-PIO1.18{slash}CT16B1C1{slash}TXD-Pad28)") (class "Default")
      (node (ref "IC1") (pin "28") (pinfunction "PIO1.18/CT16B1C1/TXD_28") (pintype "bidirectional"))
    )
    (net (code "73") (name "unconnected-(IC1-PIO1.23{slash}CT16B1M1{slash}SSEL1-Pad24)") (class "Default")
      (node (ref "IC1") (pin "24") (pinfunction "PIO1.23/CT16B1M1/SSEL1_24") (pintype "bidirectional"))
    )
    (net (code "74") (name "unconnected-(IC1-PIO1.24{slash}CT32B0M0-Pad27)") (class "Default")
      (node (ref "IC1") (pin "27") (pinfunction "PIO1.24/CT32B0M0_27") (pintype "bidirectional"))
    )
    (net (code "75") (name "unconnected-(IC1-PIO1.26{slash}CT32B0M2{slash}RXD-Pad14)") (class "Default")
      (node (ref "IC1") (pin "14") (pinfunction "PIO1.26/CT32B0M2/RXD_14") (pintype "bidirectional"))
    )
    (net (code "76") (name "unconnected-(IC1-PIO1.27{slash}CT32B0M3{slash}TXD-Pad15)") (class "Default")
      (node (ref "IC1") (pin "15") (pinfunction "PIO1.27/CT32B0M3/TXD_15") (pintype "bidirectional"))
    )
    (net (code "77") (name "unconnected-(IC1-PIO1.28{slash}CT32B0C0{slash}SCLK-Pad31)") (class "Default")
      (node (ref "IC1") (pin "31") (pinfunction "PIO1.28/CT32B0C0/SCLK_31") (pintype "bidirectional"))
    )
    (net (code "78") (name "unconnected-(IC1-PIO1.29{slash}SCK0{slash}CT32B0C1-Pad41)") (class "Default")
      (node (ref "IC1") (pin "41") (pinfunction "PIO1.29/SCK0/CT32B0C1_41") (pintype "bidirectional"))
    )
    (net (code "79") (name "unconnected-(IC1-TDI{slash}PIO0.11{slash}AD0{slash}CT32B0M3-Pad42)") (class "Default")
      (node (ref "IC1") (pin "42") (pinfunction "TDI/PIO0.11/AD0/CT32B0M3_42") (pintype "bidirectional"))
    )
    (net (code "80") (name "unconnected-(IC1-TMS{slash}PIO0.12{slash}AD1{slash}CT32B1M0-Pad44)") (class "Default")
      (node (ref "IC1") (pin "44") (pinfunction "TMS/PIO0.12/AD1/CT32B1M0_44") (pintype "bidirectional"))
    )
    (net (code "81") (name "unconnected-(JTAG1-Pad8)") (class "Default")
      (node (ref "JTAG1") (pin "8") (pinfunction "8_8") (pintype "passive"))
    )
    (net (code "82") (name "unconnected-(SW_MODE-1-PadP$1)") (class "Default")
      (node (ref "SW_MODE") (pin "P$1") (pinfunction "1_P$1") (pintype "passive"))
    )
    (net (code "83") (name "unconnected-(SW_MODE-4-PadP$4)") (class "Default")
      (node (ref "SW_MODE") (pin "P$4") (pinfunction "4_P$4") (pintype "passive"))
    )
    (net (code "84") (name "unconnected-(SW_PWR-1-PadP$1)") (class "Default")
      (node (ref "SW_PWR") (pin "P$1") (pinfunction "1_P$1") (pintype "passive"))
    )
    (net (code "85") (name "unconnected-(SW_PWR-3-PadP$3)") (class "Default")
      (node (ref "SW_PWR") (pin "P$3") (pinfunction "3_P$3") (pintype "passive"))
    )
    (net (code "86") (name "unconnected-(U1-NC-Pad1)") (class "Default")
      (node (ref "U1") (pin "1") (pinfunction "NC_1") (pintype "bidirectional"))
    )
    (net (code "87") (name "unconnected-(U1-RSV-Pad8)") (class "Default")
      (node (ref "U1") (pin "8") (pinfunction "RSV_8") (pintype "bidirectional"))
    )
    (net (code "88") (name "unconnected-(U1-SHIELD-PadCD1)") (class "Default")
      (node (ref "U1") (pin "CD1") (pinfunction "SHIELD_CD1") (pintype "bidirectional"))
    )
    (net (code "89") (name "unconnected-(U2-CLKOUT-Pad22)") (class "Default")
      (node (ref "U2") (pin "22") (pinfunction "CLKOUT_22") (pintype "bidirectional"))
    )
    (net (code "90") (name "unconnected-(U5-*INT{slash}SQW-Pad3)") (class "Default")
      (node (ref "U5") (pin "3") (pinfunction "*INT/SQW_3") (pintype "passive"))
    )
    (net (code "91") (name "unconnected-(U5-32KHZ-Pad1)") (class "Default")
      (node (ref "U5") (pin "1") (pinfunction "32KHZ_1") (pintype "passive"))
    )
    (net (code "92") (name "unconnected-(U8-*OUT-Pad4)") (class "Default")
      (node (ref "U8") (pin "4") (pinfunction "*OUT_4") (pintype "output"))
    )
    (net (code "93") (name "unconnected-(U9-AIO0-Pad9)") (class "Default")
      (node (ref "U9") (pin "9") (pinfunction "AIO0_9") (pintype "bidirectional"))
    )
    (net (code "94") (name "unconnected-(U9-AIO1-Pad10)") (class "Default")
      (node (ref "U9") (pin "10") (pinfunction "AIO1_10") (pintype "bidirectional"))
    )
    (net (code "95") (name "unconnected-(U9-CLK-Pad19)") (class "Default")
      (node (ref "U9") (pin "19") (pinfunction "CLK_19") (pintype "bidirectional"))
    )
    (net (code "96") (name "unconnected-(U9-CSB-Pad16)") (class "Default")
      (node (ref "U9") (pin "16") (pinfunction "CSB_16") (pintype "bidirectional"))
    )
    (net (code "97") (name "unconnected-(U9-CTS-Pad3)") (class "Default")
      (node (ref "U9") (pin "3") (pinfunction "CTS_3") (pintype "bidirectional"))
    )
    (net (code "98") (name "unconnected-(U9-GND1-Pad21)") (class "Default")
      (node (ref "U9") (pin "21") (pinfunction "GND1_21") (pintype "bidirectional"))
    )
    (net (code "99") (name "unconnected-(U9-GND2-Pad22)") (class "Default")
      (node (ref "U9") (pin "22") (pinfunction "GND2_22") (pintype "bidirectional"))
    )
    (net (code "100") (name "unconnected-(U9-MISO-Pad18)") (class "Default")
      (node (ref "U9") (pin "18") (pinfunction "MISO_18") (pintype "bidirectional"))
    )
    (net (code "101") (name "unconnected-(U9-MOSI-Pad17)") (class "Default")
      (node (ref "U9") (pin "17") (pinfunction "MOSI_17") (pintype "bidirectional"))
    )
    (net (code "102") (name "unconnected-(U9-NC-Pad14)") (class "Default")
      (node (ref "U9") (pin "14") (pinfunction "NC_14") (pintype "bidirectional"))
    )
    (net (code "103") (name "unconnected-(U9-PCM_CLK-Pad5)") (class "Default")
      (node (ref "U9") (pin "5") (pinfunction "PCM_CLK_5") (pintype "bidirectional"))
    )
    (net (code "104") (name "unconnected-(U9-PCM_IN-Pad7)") (class "Default")
      (node (ref "U9") (pin "7") (pinfunction "PCM_IN_7") (pintype "bidirectional"))
    )
    (net (code "105") (name "unconnected-(U9-PCM_OUT-Pad6)") (class "Default")
      (node (ref "U9") (pin "6") (pinfunction "PCM_OUT_6") (pintype "bidirectional"))
    )
    (net (code "106") (name "unconnected-(U9-PCN_SYNC-Pad8)") (class "Default")
      (node (ref "U9") (pin "8") (pinfunction "PCN_SYNC_8") (pintype "bidirectional"))
    )
    (net (code "107") (name "unconnected-(U9-PIO0-Pad23)") (class "Default")
      (node (ref "U9") (pin "23") (pinfunction "PIO0_23") (pintype "bidirectional"))
    )
    (net (code "108") (name "unconnected-(U9-PIO1-Pad24)") (class "Default")
      (node (ref "U9") (pin "24") (pinfunction "PIO1_24") (pintype "bidirectional"))
    )
    (net (code "109") (name "unconnected-(U9-PIO2-Pad25)") (class "Default")
      (node (ref "U9") (pin "25") (pinfunction "PIO2_25") (pintype "bidirectional"))
    )
    (net (code "110") (name "unconnected-(U9-PIO4-Pad27)") (class "Default")
      (node (ref "U9") (pin "27") (pinfunction "PIO4_27") (pintype "bidirectional"))
    )
    (net (code "111") (name "unconnected-(U9-PIO5-Pad28)") (class "Default")
      (node (ref "U9") (pin "28") (pinfunction "PIO5_28") (pintype "bidirectional"))
    )
    (net (code "112") (name "unconnected-(U9-PIO6-Pad29)") (class "Default")
      (node (ref "U9") (pin "29") (pinfunction "PIO6_29") (pintype "bidirectional"))
    )
    (net (code "113") (name "unconnected-(U9-PIO7-Pad30)") (class "Default")
      (node (ref "U9") (pin "30") (pinfunction "PIO7_30") (pintype "bidirectional"))
    )
    (net (code "114") (name "unconnected-(U9-PIO8-Pad31)") (class "Default")
      (node (ref "U9") (pin "31") (pinfunction "PIO8_31") (pintype "bidirectional"))
    )
    (net (code "115") (name "unconnected-(U9-PIO9-Pad32)") (class "Default")
      (node (ref "U9") (pin "32") (pinfunction "PIO9_32") (pintype "bidirectional"))
    )
    (net (code "116") (name "unconnected-(U9-PIO10-Pad33)") (class "Default")
      (node (ref "U9") (pin "33") (pinfunction "PIO10_33") (pintype "bidirectional"))
    )
    (net (code "117") (name "unconnected-(U9-RTS-Pad4)") (class "Default")
      (node (ref "U9") (pin "4") (pinfunction "RTS_4") (pintype "bidirectional"))
    )
    (net (code "118") (name "unconnected-(U9-VBUSD+-Pad20)") (class "Default")
      (node (ref "U9") (pin "20") (pinfunction "VBUSD+_20") (pintype "bidirectional"))
    )
    (net (code "119") (name "unconnected-(U9-VBUSD--Pad15)") (class "Default")
      (node (ref "U9") (pin "15") (pinfunction "VBUSD-_15") (pintype "bidirectional"))
    )
  )
)
